# Ethernet.net
KiCad netlist of a schematic drawn in Altium Designer
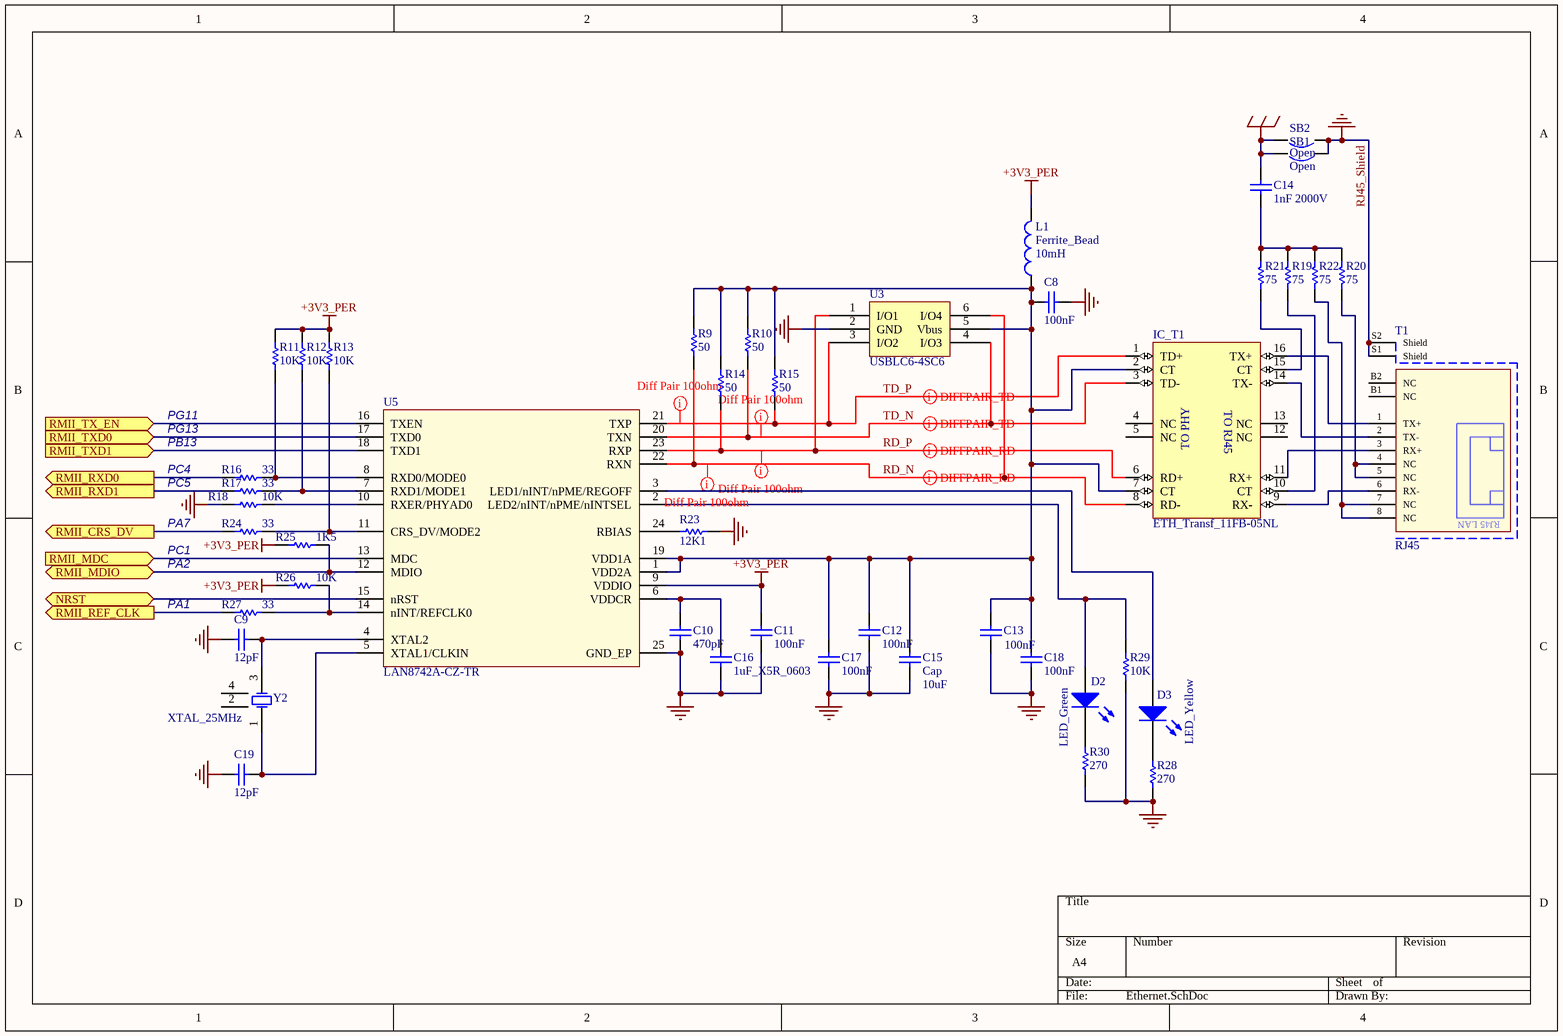
[diagram p0: Ethernet.SchDoc]

(export (version "E")
  (design (tool "Eeschema 10.0.6"))
  (components
    (comp (ref "C8")
      (value "100nF")
      (footprint "C0603")
      (description "Capacitor 0402 / 0603 / 0805")
      (libsource (lib "MCD_TOOLS") (part "Capacitor_ST"))
    )
    (comp (ref "C9")
      (value "12pF")
      (footprint "C0603")
      (description "Capacitor 0402 / 0603 / 0805")
      (libsource (lib "MCD_TOOLS") (part "Capacitor_ST"))
    )
    (comp (ref "C10")
      (value "470pF")
      (footprint "C0603")
      (description "Capacitor 0402 / 0603 / 0805")
      (libsource (lib "MCD_TOOLS") (part "Capacitor_ST"))
    )
    (comp (ref "C11")
      (value "100nF")
      (footprint "C0603")
      (description "Capacitor 0402 / 0603 / 0805")
      (libsource (lib "MCD_TOOLS") (part "Capacitor_ST"))
    )
    (comp (ref "C12")
      (value "100nF")
      (footprint "C0603")
      (description "Capacitor 0402 / 0603 / 0805")
      (libsource (lib "MCD_TOOLS") (part "Capacitor_ST"))
    )
    (comp (ref "C13")
      (value "100nF")
      (footprint "C0603")
      (description "Capacitor 0402 / 0603 / 0805")
      (libsource (lib "MCD_TOOLS") (part "Capacitor_ST"))
    )
    (comp (ref "C14")
      (value "1nF 2000V")
      (footprint "C1206")
      (description "Capacitor 0402 / 0603 / 0805/ 1206")
      (libsource (lib "MCD_TOOLS") (part "Capacitor_ST"))
    )
    (comp (ref "C15")
      (value "Cap")
      (footprint "C0805")
      (description "Capacitor")
      (fields (field (name "ALTIUM_VALUE") "10uF") (field (name "PUBLISHER") "Altium Limited"))
      (libsource (lib "cadLib") (part "Cap"))
    )
    (comp (ref "C16")
      (value "1uF_X5R_0603")
      (footprint "C0603")
      (description "0603  X5R 1µF")
      (fields (field (name "TOLERANCE") "10%"))
      (libsource (lib "MB963_1") (part "CAP SMD 0603  X5R 1µF 25V 10%"))
    )
    (comp (ref "C17")
      (value "100nF")
      (footprint "C0603")
      (description "Capacitor 0402 / 0603 / 0805")
      (libsource (lib "MCD_TOOLS") (part "Capacitor_ST"))
    )
    (comp (ref "C18")
      (value "100nF")
      (footprint "C0603")
      (description "Capacitor 0402 / 0603 / 0805")
      (libsource (lib "MCD_TOOLS") (part "Capacitor_ST"))
    )
    (comp (ref "C19")
      (value "12pF")
      (footprint "C0603")
      (description "Capacitor 0402 / 0603 / 0805")
      (libsource (lib "MCD_TOOLS") (part "Capacitor_ST"))
    )
    (comp (ref "D2")
      (value "LED_Green")
      (footprint "0603_LED")
      (description "SMD LED")
      (fields (field (name "PUBLISHER") "Altium Limited"))
      (libsource (lib "cadLib") (part "LED"))
    )
    (comp (ref "D3")
      (value "LED_Yellow")
      (footprint "0603_LED")
      (description "SMD LED")
      (fields (field (name "PUBLISHER") "Altium Limited"))
      (libsource (lib "cadLib") (part "LED"))
    )
    (comp (ref "IC_T1")
      (value "ETH_Transf_11FB-05NL")
      (footprint "ETH_Transf 11FB-05NL")
      (libsource (lib "cadLib") (part "ETH_Transf_11FB-05NL"))
    )
    (comp (ref "L1")
      (value "Ferrite_Bead")
      (footprint "0805")
      (fields (field (name "ALTIUM_VALUE") "10mH") (field (name "PUBLISHER") "Altium Limited"))
      (libsource (lib "cadLib") (part "Ferrite_Bead"))
    )
    (comp (ref "R9")
      (value "50")
      (footprint "R0603")
      (description "Resistor,50,0603,1%,YAGEO")
      (libsource (lib "MB1137") (part "Res_50_1%_0603"))
    )
    (comp (ref "R10")
      (value "50")
      (footprint "R0603")
      (description "Resistor,50,0603,1%,YAGEO")
      (libsource (lib "MB1137") (part "Res_50_1%_0603"))
    )
    (comp (ref "R11")
      (value "10K")
      (footprint "R0603")
      (description "Resistor 0402 / 0603 / 0805")
      (libsource (lib "Miscellaneous Devices") (part "Res1"))
    )
    (comp (ref "R12")
      (value "10K")
      (footprint "R0603")
      (description "Resistor 0402 / 0603 / 0805")
      (libsource (lib "Miscellaneous Devices") (part "Res1"))
    )
    (comp (ref "R13")
      (value "10K")
      (footprint "R0603")
      (description "Resistor 0402 / 0603 / 0805")
      (libsource (lib "Miscellaneous Devices") (part "Res1"))
    )
    (comp (ref "R14")
      (value "50")
      (footprint "R0603")
      (description "Resistor,50,0603,1%,YAGEO")
      (libsource (lib "MB1137") (part "Res_50_1%_0603"))
    )
    (comp (ref "R15")
      (value "50")
      (footprint "R0603")
      (description "Resistor,50,0603,1%,YAGEO")
      (libsource (lib "MB1137") (part "Res_50_1%_0603"))
    )
    (comp (ref "R16")
      (value "33")
      (footprint "R0603")
      (description "Resistor,33,0402,1%,YAGEO")
      (libsource (lib "MCD_TOOLS") (part "Res_33_1%_0402"))
    )
    (comp (ref "R17")
      (value "33")
      (footprint "R0603")
      (description "Resistor,33,0402,1%,YAGEO")
      (libsource (lib "MCD_TOOLS") (part "Res_33_1%_0402"))
    )
    (comp (ref "R18")
      (value "10K")
      (footprint "R0603")
      (description "Resistor 0402 / 0603 / 0805")
      (libsource (lib "Miscellaneous Devices") (part "Res1"))
    )
    (comp (ref "R19")
      (value "75")
      (footprint "R0603")
      (description "Resistor,75,0603,1%,YAGEO")
      (libsource (lib "MB1137") (part "Res_75_1%_0603"))
    )
    (comp (ref "R20")
      (value "75")
      (footprint "R0603")
      (description "Resistor,75,0603,1%,YAGEO")
      (libsource (lib "MB1137") (part "Res_75_1%_0603"))
    )
    (comp (ref "R21")
      (value "75")
      (footprint "R0603")
      (description "Resistor,75,0603,1%,YAGEO")
      (libsource (lib "MB1137") (part "Res_75_1%_0603"))
    )
    (comp (ref "R22")
      (value "75")
      (footprint "R0603")
      (description "Resistor,75,0603,1%,YAGEO")
      (libsource (lib "MB1137") (part "Res_75_1%_0603"))
    )
    (comp (ref "R23")
      (value "12K1")
      (footprint "R0805")
      (description "Resistor,12K1,0603,1%,VISHAY")
      (libsource (lib "MCD_TOOLS") (part "Res_12K1_1%_0603"))
    )
    (comp (ref "R24")
      (value "33")
      (footprint "R0603")
      (description "Resistor,33,0402,1%,YAGEO")
      (libsource (lib "MCD_TOOLS") (part "Res_33_1%_0402"))
    )
    (comp (ref "R25")
      (value "1K5")
      (footprint "R0603")
      (description "Resistor,1K5,0402,1%,YAGEO")
      (libsource (lib "MCD_TOOLS") (part "Res_1K5_1%_0402"))
    )
    (comp (ref "R26")
      (value "10K")
      (footprint "R0603")
      (description "Resistor 0402 / 0603 / 0805")
      (libsource (lib "Miscellaneous Devices") (part "Res1"))
    )
    (comp (ref "R27")
      (value "33")
      (footprint "R0603")
      (description "Resistor,33,0402,1%,YAGEO")
      (libsource (lib "MCD_TOOLS") (part "Res_33_1%_0402"))
    )
    (comp (ref "R28")
      (value "270")
      (footprint "R0603")
      (description "Resistor 0402 / 0603 / 0805")
      (libsource (lib "Miscellaneous Devices") (part "Res1"))
    )
    (comp (ref "R29")
      (value "10K")
      (footprint "R0603")
      (description "Resistor 0402 / 0603 / 0805")
      (libsource (lib "Miscellaneous Devices") (part "Res1"))
    )
    (comp (ref "R30")
      (value "270")
      (footprint "R0603")
      (description "Resistor 0402 / 0603 / 0805")
      (libsource (lib "Miscellaneous Devices") (part "Res1"))
    )
    (comp (ref "SB1")
      (value "Open")
      (footprint "SB_0603")
      (description "Circuit Breaker")
      (fields (field (name "PUBLISHER") "Altium Limited"))
      (libsource (lib "cadLib") (part "Circuit Breaker"))
    )
    (comp (ref "SB2")
      (value "Open")
      (footprint "SB_0603")
      (description "Circuit Breaker")
      (fields (field (name "PUBLISHER") "Altium Limited"))
      (libsource (lib "cadLib") (part "Circuit Breaker"))
    )
    (comp (ref "T1")
      (value "RJ45")
      (footprint "RJ45_ETH")
      (description "WE-RJ45 LAN Transformer, 10/100 Base-T, THT, Port 1x1, Tab Up")
      (fields (field (name "PART NUMBER") "7499010003A") (field (name "PUBLISHER") "Wurth Elektronik"))
      (libsource (lib "cadLib") (part "RJ45"))
    )
    (comp (ref "U3")
      (value "USBLC6-4SC6")
      (footprint "SOT23-6L")
      (libsource (lib "MB1137_1") (part "USBLC6-4SC6"))
    )
    (comp (ref "U5")
      (value "LAN8742A-CZ-TR")
      (footprint "QFN24_0R5_4X4")
      (libsource (lib "MB1137") (part "LAN8742A-CZ-TR"))
    )
    (comp (ref "Y2")
      (value "XTAL_25MHz")
      (footprint "SMD-3225_4P")
      (description "Crystal")
      (fields (field (name "PUBLISHER") "Altium Limited"))
      (libsource (lib "cadLib") (part "XTAL_SMD"))
    )
  )
  (nets
    (net (code "1") (name "+3V3_PER") (class "Default")
      (node (ref "C11") (pin "2") (pinfunction "2_2") (pintype "passive"))
      (node (ref "L1") (pin "2") (pinfunction "2_2") (pintype "passive"))
      (node (ref "R11") (pin "1") (pinfunction "1_1") (pintype "passive"))
      (node (ref "R12") (pin "1") (pinfunction "1_1") (pintype "passive"))
      (node (ref "R13") (pin "1") (pinfunction "1_1") (pintype "passive"))
      (node (ref "R25") (pin "2") (pinfunction "2_2") (pintype "passive"))
      (node (ref "R26") (pin "1") (pinfunction "1_1") (pintype "passive"))
      (node (ref "U5") (pin "9") (pinfunction "VDDIO_9") (pintype "passive"))
    )
    (net (code "2") (name "/NRST") (class "Default")
      (node (ref "U5") (pin "15") (pinfunction "nRST_15") (pintype "passive"))
    )
    (net (code "3") (name "/RD_N") (class "Default")
      (node (ref "IC_T1") (pin "8") (pinfunction "RD-_8") (pintype "bidirectional"))
      (node (ref "R9") (pin "1") (pinfunction "1_1") (pintype "passive"))
      (node (ref "U3") (pin "6") (pinfunction "I/O4_6") (pintype "passive"))
      (node (ref "U5") (pin "22") (pinfunction "RXN_22") (pintype "passive"))
    )
    (net (code "4") (name "/RD_P") (class "Default")
      (node (ref "IC_T1") (pin "6") (pinfunction "RD+_6") (pintype "bidirectional"))
      (node (ref "R14") (pin "1") (pinfunction "1_1") (pintype "passive"))
      (node (ref "U3") (pin "1") (pinfunction "I/O1_1") (pintype "passive"))
      (node (ref "U5") (pin "23") (pinfunction "RXP_23") (pintype "passive"))
    )
    (net (code "5") (name "/RMII_CRS_DV") (class "Default")
      (node (ref "R24") (pin "2") (pinfunction "2_2") (pintype "passive"))
    )
    (net (code "6") (name "/RMII_MDC") (class "Default")
      (node (ref "U5") (pin "13") (pinfunction "MDC_13") (pintype "passive"))
    )
    (net (code "7") (name "/RMII_MDIO") (class "Default")
      (node (ref "R25") (pin "1") (pinfunction "1_1") (pintype "passive"))
      (node (ref "U5") (pin "12") (pinfunction "MDIO_12") (pintype "passive"))
    )
    (net (code "8") (name "/RMII_REF_CLK") (class "Default")
      (node (ref "R27") (pin "2") (pinfunction "2_2") (pintype "passive"))
    )
    (net (code "9") (name "/RMII_RXD0") (class "Default")
      (node (ref "R16") (pin "2") (pinfunction "2_2") (pintype "passive"))
    )
    (net (code "10") (name "/RMII_RXD1") (class "Default")
      (node (ref "R17") (pin "2") (pinfunction "2_2") (pintype "passive"))
    )
    (net (code "11") (name "/RMII_TXD0") (class "Default")
      (node (ref "U5") (pin "17") (pinfunction "TXD0_17") (pintype "passive"))
    )
    (net (code "12") (name "/RMII_TXD1") (class "Default")
      (node (ref "U5") (pin "18") (pinfunction "TXD1_18") (pintype "passive"))
    )
    (net (code "13") (name "/RMII_TX_EN") (class "Default")
      (node (ref "U5") (pin "16") (pinfunction "TXEN_16") (pintype "passive"))
    )
    (net (code "14") (name "/TD_N") (class "Default")
      (node (ref "IC_T1") (pin "3") (pinfunction "TD-_3") (pintype "bidirectional"))
      (node (ref "R10") (pin "1") (pinfunction "1_1") (pintype "passive"))
      (node (ref "U3") (pin "4") (pinfunction "I/O3_4") (pintype "passive"))
      (node (ref "U5") (pin "20") (pinfunction "TXN_20") (pintype "passive"))
    )
    (net (code "15") (name "/TD_P") (class "Default")
      (node (ref "IC_T1") (pin "1") (pinfunction "TD+_1") (pintype "bidirectional"))
      (node (ref "R15") (pin "1") (pinfunction "1_1") (pintype "passive"))
      (node (ref "U3") (pin "3") (pinfunction "I/O2_3") (pintype "passive"))
      (node (ref "U5") (pin "21") (pinfunction "TXP_21") (pintype "passive"))
    )
    (net (code "16") (name "EGND") (class "Default")
      (node (ref "C14") (pin "1") (pinfunction "1_1") (pintype "passive"))
      (node (ref "SB1") (pin "1") (pinfunction "1_1") (pintype "passive"))
      (node (ref "SB2") (pin "1") (pinfunction "1_1") (pintype "passive"))
    )
    (net (code "17") (name "GND") (class "Default")
      (node (ref "C10") (pin "1") (pinfunction "1_1") (pintype "passive"))
      (node (ref "C11") (pin "1") (pinfunction "1_1") (pintype "passive"))
      (node (ref "C12") (pin "1") (pinfunction "1_1") (pintype "passive"))
      (node (ref "C13") (pin "1") (pinfunction "1_1") (pintype "passive"))
      (node (ref "C15") (pin "1") (pinfunction "1_1") (pintype "passive"))
      (node (ref "C16") (pin "2") (pinfunction "2_2") (pintype "passive"))
      (node (ref "C17") (pin "1") (pinfunction "1_1") (pintype "passive"))
      (node (ref "C18") (pin "1") (pinfunction "1_1") (pintype "passive"))
      (node (ref "C19") (pin "2") (pinfunction "2_2") (pintype "passive"))
      (node (ref "C8") (pin "1") (pinfunction "1_1") (pintype "passive"))
      (node (ref "C9") (pin "2") (pinfunction "2_2") (pintype "passive"))
      (node (ref "R18") (pin "2") (pinfunction "2_2") (pintype "passive"))
      (node (ref "R23") (pin "2") (pinfunction "2_2") (pintype "passive"))
      (node (ref "R28") (pin "2") (pinfunction "2_2") (pintype "passive"))
      (node (ref "R29") (pin "2") (pinfunction "2_2") (pintype "passive"))
      (node (ref "R30") (pin "2") (pinfunction "2_2") (pintype "passive"))
      (node (ref "SB1") (pin "2") (pinfunction "2_2") (pintype "passive"))
      (node (ref "SB2") (pin "2") (pinfunction "2_2") (pintype "passive"))
      (node (ref "T1") (pin "S1") (pinfunction "Shield_S1") (pintype "passive"))
      (node (ref "T1") (pin "S2") (pinfunction "Shield_S2") (pintype "passive"))
      (node (ref "U3") (pin "2") (pinfunction "GND_2") (pintype "passive"))
      (node (ref "U5") (pin "25") (pinfunction "GND_EP_25") (pintype "passive"))
    )
    (net (code "18") (name "Net-(C14-Pad2)") (class "Default")
      (node (ref "C14") (pin "2") (pinfunction "2_2") (pintype "passive"))
      (node (ref "R19") (pin "1") (pinfunction "1_1") (pintype "passive"))
      (node (ref "R20") (pin "1") (pinfunction "1_1") (pintype "passive"))
      (node (ref "R21") (pin "1") (pinfunction "1_1") (pintype "passive"))
      (node (ref "R22") (pin "1") (pinfunction "1_1") (pintype "passive"))
    )
    (net (code "19") (name "Net-(D2-A)") (class "Default")
      (node (ref "D2") (pin "2") (pinfunction "A_2") (pintype "passive"))
      (node (ref "R29") (pin "1") (pinfunction "1_1") (pintype "passive"))
      (node (ref "U5") (pin "2") (pinfunction "LED2/nINT/nPME/nINTSEL_2") (pintype "passive"))
    )
    (net (code "20") (name "Net-(D2-K)") (class "Default")
      (node (ref "D2") (pin "1") (pinfunction "K_1") (pintype "passive"))
      (node (ref "R30") (pin "1") (pinfunction "1_1") (pintype "passive"))
    )
    (net (code "21") (name "Net-(D3-A)") (class "Default")
      (node (ref "D3") (pin "2") (pinfunction "A_2") (pintype "passive"))
      (node (ref "U5") (pin "3") (pinfunction "LED1/nINT/nPME/REGOFF_3") (pintype "passive"))
    )
    (net (code "22") (name "Net-(D3-K)") (class "Default")
      (node (ref "D3") (pin "1") (pinfunction "K_1") (pintype "passive"))
      (node (ref "R28") (pin "1") (pinfunction "1_1") (pintype "passive"))
    )
    (net (code "23") (name "Net-(IC_T1-CT-Pad10)") (class "Default")
      (node (ref "IC_T1") (pin "10") (pinfunction "CT_10") (pintype "bidirectional"))
      (node (ref "R19") (pin "2") (pinfunction "2_2") (pintype "passive"))
    )
    (net (code "24") (name "Net-(IC_T1-CT-Pad15)") (class "Default")
      (node (ref "IC_T1") (pin "15") (pinfunction "CT_15") (pintype "bidirectional"))
      (node (ref "R21") (pin "2") (pinfunction "2_2") (pintype "passive"))
    )
    (net (code "25") (name "Net-(IC_T1-RX+)") (class "Default")
      (node (ref "IC_T1") (pin "11") (pinfunction "RX+_11") (pintype "bidirectional"))
      (node (ref "T1") (pin "3") (pinfunction "RX+_3") (pintype "passive"))
    )
    (net (code "26") (name "Net-(IC_T1-RX-)") (class "Default")
      (node (ref "IC_T1") (pin "9") (pinfunction "RX-_9") (pintype "bidirectional"))
      (node (ref "T1") (pin "6") (pinfunction "RX-_6") (pintype "passive"))
    )
    (net (code "27") (name "Net-(IC_T1-TX+)") (class "Default")
      (node (ref "IC_T1") (pin "16") (pinfunction "TX+_16") (pintype "bidirectional"))
      (node (ref "T1") (pin "1") (pinfunction "TX+_1") (pintype "passive"))
    )
    (net (code "28") (name "Net-(IC_T1-TX-)") (class "Default")
      (node (ref "IC_T1") (pin "14") (pinfunction "TX-_14") (pintype "bidirectional"))
      (node (ref "T1") (pin "2") (pinfunction "TX-_2") (pintype "passive"))
    )
    (net (code "29") (name "Net-(R20-Pad2)") (class "Default")
      (node (ref "R20") (pin "2") (pinfunction "2_2") (pintype "passive"))
      (node (ref "T1") (pin "4") (pinfunction "NC_4") (pintype "passive"))
      (node (ref "T1") (pin "5") (pinfunction "NC_5") (pintype "passive"))
    )
    (net (code "30") (name "Net-(R22-Pad2)") (class "Default")
      (node (ref "R22") (pin "2") (pinfunction "2_2") (pintype "passive"))
      (node (ref "T1") (pin "7") (pinfunction "NC_7") (pintype "passive"))
      (node (ref "T1") (pin "8") (pinfunction "NC_8") (pintype "passive"))
    )
    (net (code "31") (name "Net-(U3-Vbus)") (class "Default")
      (node (ref "C12") (pin "2") (pinfunction "2_2") (pintype "passive"))
      (node (ref "C13") (pin "2") (pinfunction "2_2") (pintype "passive"))
      (node (ref "C15") (pin "2") (pinfunction "2_2") (pintype "passive"))
      (node (ref "C17") (pin "2") (pinfunction "2_2") (pintype "passive"))
      (node (ref "C18") (pin "2") (pinfunction "2_2") (pintype "passive"))
      (node (ref "C8") (pin "2") (pinfunction "2_2") (pintype "passive"))
      (node (ref "IC_T1") (pin "2") (pinfunction "CT_2") (pintype "bidirectional"))
      (node (ref "IC_T1") (pin "7") (pinfunction "CT_7") (pintype "bidirectional"))
      (node (ref "L1") (pin "1") (pinfunction "1_1") (pintype "passive"))
      (node (ref "R10") (pin "2") (pinfunction "2_2") (pintype "passive"))
      (node (ref "R14") (pin "2") (pinfunction "2_2") (pintype "passive"))
      (node (ref "R15") (pin "2") (pinfunction "2_2") (pintype "passive"))
      (node (ref "R9") (pin "2") (pinfunction "2_2") (pintype "passive"))
      (node (ref "U3") (pin "5") (pinfunction "Vbus_5") (pintype "passive"))
      (node (ref "U5") (pin "1") (pinfunction "VDD2A_1") (pintype "passive"))
      (node (ref "U5") (pin "19") (pinfunction "VDD1A_19") (pintype "passive"))
    )
    (net (code "32") (name "Net-(U5-CRS_DV{slash}MODE2)") (class "Default")
      (node (ref "R13") (pin "2") (pinfunction "2_2") (pintype "passive"))
      (node (ref "R24") (pin "1") (pinfunction "1_1") (pintype "passive"))
      (node (ref "U5") (pin "11") (pinfunction "CRS_DV/MODE2_11") (pintype "passive"))
    )
    (net (code "33") (name "Net-(U5-RBIAS)") (class "Default")
      (node (ref "R23") (pin "1") (pinfunction "1_1") (pintype "passive"))
      (node (ref "U5") (pin "24") (pinfunction "RBIAS_24") (pintype "passive"))
    )
    (net (code "34") (name "Net-(U5-RXD0{slash}MODE0)") (class "Default")
      (node (ref "R11") (pin "2") (pinfunction "2_2") (pintype "passive"))
      (node (ref "R16") (pin "1") (pinfunction "1_1") (pintype "passive"))
      (node (ref "U5") (pin "8") (pinfunction "RXD0/MODE0_8") (pintype "passive"))
    )
    (net (code "35") (name "Net-(U5-RXD1{slash}MODE1)") (class "Default")
      (node (ref "R12") (pin "2") (pinfunction "2_2") (pintype "passive"))
      (node (ref "R17") (pin "1") (pinfunction "1_1") (pintype "passive"))
      (node (ref "U5") (pin "7") (pinfunction "RXD1/MODE1_7") (pintype "passive"))
    )
    (net (code "36") (name "Net-(U5-RXER{slash}PHYAD0)") (class "Default")
      (node (ref "R18") (pin "1") (pinfunction "1_1") (pintype "passive"))
      (node (ref "U5") (pin "10") (pinfunction "RXER/PHYAD0_10") (pintype "passive"))
    )
    (net (code "37") (name "Net-(U5-VDDCR)") (class "Default")
      (node (ref "C10") (pin "2") (pinfunction "2_2") (pintype "passive"))
      (node (ref "C16") (pin "1") (pinfunction "1_1") (pintype "passive"))
      (node (ref "U5") (pin "6") (pinfunction "VDDCR_6") (pintype "passive"))
    )
    (net (code "38") (name "Net-(U5-XTAL1{slash}CLKIN)") (class "Default")
      (node (ref "C19") (pin "1") (pinfunction "1_1") (pintype "passive"))
      (node (ref "U5") (pin "5") (pinfunction "XTAL1/CLKIN_5") (pintype "passive"))
      (node (ref "Y2") (pin "1") (pinfunction "OSC1_1") (pintype "passive"))
    )
    (net (code "39") (name "Net-(U5-XTAL2)") (class "Default")
      (node (ref "C9") (pin "1") (pinfunction "1_1") (pintype "passive"))
      (node (ref "U5") (pin "4") (pinfunction "XTAL2_4") (pintype "passive"))
      (node (ref "Y2") (pin "3") (pinfunction "OSC2_3") (pintype "passive"))
    )
    (net (code "40") (name "Net-(U5-nINT{slash}REFCLK0)") (class "Default")
      (node (ref "R26") (pin "2") (pinfunction "2_2") (pintype "passive"))
      (node (ref "R27") (pin "1") (pinfunction "1_1") (pintype "passive"))
      (node (ref "U5") (pin "14") (pinfunction "nINT/REFCLK0_14") (pintype "passive"))
    )
    (net (code "41") (name "unconnected-(IC_T1-NC-Pad4)") (class "Default")
      (node (ref "IC_T1") (pin "4") (pinfunction "NC_4") (pintype "passive"))
    )
    (net (code "42") (name "unconnected-(IC_T1-NC-Pad5)") (class "Default")
      (node (ref "IC_T1") (pin "5") (pinfunction "NC_5") (pintype "passive"))
    )
    (net (code "43") (name "unconnected-(IC_T1-NC-Pad12)") (class "Default")
      (node (ref "IC_T1") (pin "12") (pinfunction "NC_12") (pintype "passive"))
    )
    (net (code "44") (name "unconnected-(IC_T1-NC-Pad13)") (class "Default")
      (node (ref "IC_T1") (pin "13") (pinfunction "NC_13") (pintype "passive"))
    )
    (net (code "45") (name "unconnected-(T1-NC-PadB1)") (class "Default")
      (node (ref "T1") (pin "B1") (pinfunction "NC_B1") (pintype "passive"))
    )
    (net (code "46") (name "unconnected-(T1-NC-PadB2)") (class "Default")
      (node (ref "T1") (pin "B2") (pinfunction "NC_B2") (pintype "passive"))
    )
    (net (code "47") (name "unconnected-(Y2-OSC1-Pad2)") (class "Default")
      (node (ref "Y2") (pin "2") (pinfunction "OSC1_2") (pintype "passive"))
    )
    (net (code "48") (name "unconnected-(Y2-OSC1-Pad4)") (class "Default")
      (node (ref "Y2") (pin "4") (pinfunction "OSC1_4") (pintype "passive"))
    )
  )
)
